# 02_RPI_IO.net
KiCad netlist of a schematic drawn in Altium Designer
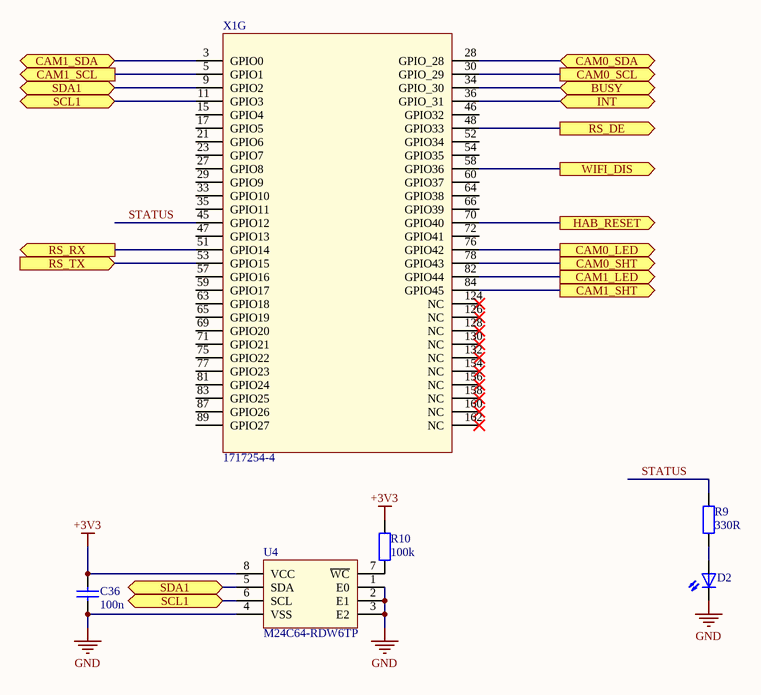
[diagram p0: 02_RPI_IO.SchDoc]

(export (version "E")
  (design (tool "Eeschema 10.0.6"))
  (components
    (comp (ref "C36")
      (value "100n")
      (footprint "C0603_IPC_HD")
      (description "CAP CER 0.1UF 16V X7R 0603")
      (fields
        (field (name "MANUFACTURER") "Samsung Electro-Mechanics")
        (field (name "MANUFACTURER PART NUMBER") "CL10B104KO8NNNC")
      )
      (libsource (lib "alfasat_lib") (part "CL10B104KO8NNNC"))
    )
    (comp (ref "D2")
      (value "LTST-C190GKT")
      (footprint "LED_0603")
      (description "LED GREEN CLEAR CHIP SMD 0603")
      (fields (field (name "MANUFACTURER") "Lite-On Inc."))
      (libsource (lib "alfasat_lib") (part "LTST-C190GKT"))
    )
    (comp (ref "R9")
      (value "330R")
      (footprint "R0603_IPC_MD")
      (description "RES SMD 330 OHM 5% 1/10W 0603")
      (fields
        (field (name "MANUFACTURER") "Bourns Inc.")
        (field (name "MANUFACTURER PART NUMBER") "CR0603-JW-331ELF")
      )
      (libsource (lib "alfasat_lib") (part "CR0603-JW-331ELF"))
    )
    (comp (ref "R10")
      (value "100k")
      (footprint "R0603_IPC_MD")
      (description "RES 100K OHM 1% 1/10W 0603")
      (fields
        (field (name "MANUFACTURER") "Bourns Inc.")
        (field (name "MANUFACTURER PART NUMBER") "RMCF0603FT100K")
      )
      (libsource (lib "alfasat_lib") (part "RMCF0603FT100K"))
    )
    (comp (ref "U4")
      (value "M24C64-RDW6TP")
      (footprint "TSSOP8_(ST)")
      (description "IC EEPROM 64K I2C 1MHZ 8TSSOP")
      (fields (field (name "MANUFACTURER") "STMicroelectronics"))
      (libsource (lib "alfasat_lib") (part "M24C64-RDW6TP"))
    )
    (comp (ref "X1")
      (value "1717254-4")
      (footprint "1717254-1")
      (description "CONN SKT SODIMM 200POS R/A SMD")
      (fields (field (name "MANUFACTURER") "TE Connectivity AMP Connectors"))
      (libsource (lib "alfasat_lib") (part "Raspberry CM Connector"))
    )
  )
  (nets
    (net (code "1") (name "+3V3") (class "Default")
      (node (ref "C36") (pin "2") (pinfunction "2_2") (pintype "passive"))
      (node (ref "R10") (pin "2") (pinfunction "2_2") (pintype "passive"))
      (node (ref "U4") (pin "8") (pinfunction "VCC_8") (pintype "passive"))
    )
    (net (code "2") (name "/BUSY") (class "Default")
      (node (ref "X1") (pin "34") (pinfunction "GPIO_30_34") (pintype "passive"))
    )
    (net (code "3") (name "/CAM0_LED") (class "Default")
      (node (ref "X1") (pin "76") (pinfunction "GPIO42_76") (pintype "passive"))
    )
    (net (code "4") (name "/CAM0_SCL") (class "Default")
      (node (ref "X1") (pin "30") (pinfunction "GPIO_29_30") (pintype "passive"))
    )
    (net (code "5") (name "/CAM0_SDA") (class "Default")
      (node (ref "X1") (pin "28") (pinfunction "GPIO_28_28") (pintype "passive"))
    )
    (net (code "6") (name "/CAM0_SHT") (class "Default")
      (node (ref "X1") (pin "78") (pinfunction "GPIO43_78") (pintype "passive"))
    )
    (net (code "7") (name "/CAM1_LED") (class "Default")
      (node (ref "X1") (pin "82") (pinfunction "GPIO44_82") (pintype "passive"))
    )
    (net (code "8") (name "/CAM1_SCL") (class "Default")
      (node (ref "X1") (pin "5") (pinfunction "GPIO1_5") (pintype "passive"))
    )
    (net (code "9") (name "/CAM1_SDA") (class "Default")
      (node (ref "X1") (pin "3") (pinfunction "GPIO0_3") (pintype "passive"))
    )
    (net (code "10") (name "/CAM1_SHT") (class "Default")
      (node (ref "X1") (pin "84") (pinfunction "GPIO45_84") (pintype "passive"))
    )
    (net (code "11") (name "/HAB_RESET") (class "Default")
      (node (ref "X1") (pin "70") (pinfunction "GPIO40_70") (pintype "passive"))
    )
    (net (code "12") (name "/INT") (class "Default")
      (node (ref "X1") (pin "36") (pinfunction "GPIO_31_36") (pintype "passive"))
    )
    (net (code "13") (name "/RS_DE") (class "Default")
      (node (ref "X1") (pin "48") (pinfunction "GPIO33_48") (pintype "passive"))
    )
    (net (code "14") (name "/RS_RX") (class "Default")
      (node (ref "X1") (pin "51") (pinfunction "GPIO14_51") (pintype "passive"))
    )
    (net (code "15") (name "/RS_TX") (class "Default")
      (node (ref "X1") (pin "53") (pinfunction "GPIO15_53") (pintype "passive"))
    )
    (net (code "16") (name "/SCL1") (class "Default")
      (node (ref "U4") (pin "6") (pinfunction "SCL_6") (pintype "passive"))
      (node (ref "X1") (pin "11") (pinfunction "GPIO3_11") (pintype "passive"))
    )
    (net (code "17") (name "/SDA1") (class "Default")
      (node (ref "U4") (pin "5") (pinfunction "SDA_5") (pintype "passive"))
      (node (ref "X1") (pin "9") (pinfunction "GPIO2_9") (pintype "passive"))
    )
    (net (code "18") (name "/STATUS") (class "Default")
      (node (ref "R9") (pin "2") (pinfunction "2_2") (pintype "passive"))
      (node (ref "X1") (pin "45") (pinfunction "GPIO12_45") (pintype "passive"))
    )
    (net (code "19") (name "/WIFI_DIS") (class "Default")
      (node (ref "X1") (pin "58") (pinfunction "GPIO36_58") (pintype "passive"))
    )
    (net (code "20") (name "GND") (class "Default")
      (node (ref "C36") (pin "1") (pinfunction "1_1") (pintype "passive"))
      (node (ref "D2") (pin "1") (pinfunction "C_1") (pintype "passive"))
      (node (ref "U4") (pin "1") (pinfunction "E0_1") (pintype "passive"))
      (node (ref "U4") (pin "2") (pinfunction "E1_2") (pintype "passive"))
      (node (ref "U4") (pin "3") (pinfunction "E2_3") (pintype "passive"))
      (node (ref "U4") (pin "4") (pinfunction "VSS_4") (pintype "passive"))
    )
    (net (code "21") (name "Net-(D2-A)") (class "Default")
      (node (ref "D2") (pin "2") (pinfunction "A_2") (pintype "passive"))
      (node (ref "R9") (pin "1") (pinfunction "1_1") (pintype "passive"))
    )
    (net (code "22") (name "Net-(U4-~{WC})") (class "Default")
      (node (ref "R10") (pin "1") (pinfunction "1_1") (pintype "passive"))
      (node (ref "U4") (pin "7") (pinfunction "~{WC}_7") (pintype "passive"))
    )
    (net (code "23") (name "unconnected-(X1G-GPIO4-Pad15)") (class "Default")
      (node (ref "X1") (pin "15") (pinfunction "GPIO4_15") (pintype "passive"))
    )
    (net (code "24") (name "unconnected-(X1G-GPIO5-Pad17)") (class "Default")
      (node (ref "X1") (pin "17") (pinfunction "GPIO5_17") (pintype "passive"))
    )
    (net (code "25") (name "unconnected-(X1G-GPIO6-Pad21)") (class "Default")
      (node (ref "X1") (pin "21") (pinfunction "GPIO6_21") (pintype "passive"))
    )
    (net (code "26") (name "unconnected-(X1G-GPIO7-Pad23)") (class "Default")
      (node (ref "X1") (pin "23") (pinfunction "GPIO7_23") (pintype "passive"))
    )
    (net (code "27") (name "unconnected-(X1G-GPIO8-Pad27)") (class "Default")
      (node (ref "X1") (pin "27") (pinfunction "GPIO8_27") (pintype "passive"))
    )
    (net (code "28") (name "unconnected-(X1G-GPIO9-Pad29)") (class "Default")
      (node (ref "X1") (pin "29") (pinfunction "GPIO9_29") (pintype "passive"))
    )
    (net (code "29") (name "unconnected-(X1G-GPIO10-Pad33)") (class "Default")
      (node (ref "X1") (pin "33") (pinfunction "GPIO10_33") (pintype "passive"))
    )
    (net (code "30") (name "unconnected-(X1G-GPIO11-Pad35)") (class "Default")
      (node (ref "X1") (pin "35") (pinfunction "GPIO11_35") (pintype "passive"))
    )
    (net (code "31") (name "unconnected-(X1G-GPIO13-Pad47)") (class "Default")
      (node (ref "X1") (pin "47") (pinfunction "GPIO13_47") (pintype "passive"))
    )
    (net (code "32") (name "unconnected-(X1G-GPIO16-Pad57)") (class "Default")
      (node (ref "X1") (pin "57") (pinfunction "GPIO16_57") (pintype "passive"))
    )
    (net (code "33") (name "unconnected-(X1G-GPIO17-Pad59)") (class "Default")
      (node (ref "X1") (pin "59") (pinfunction "GPIO17_59") (pintype "passive"))
    )
    (net (code "34") (name "unconnected-(X1G-GPIO18-Pad63)") (class "Default")
      (node (ref "X1") (pin "63") (pinfunction "GPIO18_63") (pintype "passive"))
    )
    (net (code "35") (name "unconnected-(X1G-GPIO19-Pad65)") (class "Default")
      (node (ref "X1") (pin "65") (pinfunction "GPIO19_65") (pintype "passive"))
    )
    (net (code "36") (name "unconnected-(X1G-GPIO20-Pad69)") (class "Default")
      (node (ref "X1") (pin "69") (pinfunction "GPIO20_69") (pintype "passive"))
    )
    (net (code "37") (name "unconnected-(X1G-GPIO21-Pad71)") (class "Default")
      (node (ref "X1") (pin "71") (pinfunction "GPIO21_71") (pintype "passive"))
    )
    (net (code "38") (name "unconnected-(X1G-GPIO22-Pad75)") (class "Default")
      (node (ref "X1") (pin "75") (pinfunction "GPIO22_75") (pintype "passive"))
    )
    (net (code "39") (name "unconnected-(X1G-GPIO23-Pad77)") (class "Default")
      (node (ref "X1") (pin "77") (pinfunction "GPIO23_77") (pintype "passive"))
    )
    (net (code "40") (name "unconnected-(X1G-GPIO24-Pad81)") (class "Default")
      (node (ref "X1") (pin "81") (pinfunction "GPIO24_81") (pintype "passive"))
    )
    (net (code "41") (name "unconnected-(X1G-GPIO25-Pad83)") (class "Default")
      (node (ref "X1") (pin "83") (pinfunction "GPIO25_83") (pintype "passive"))
    )
    (net (code "42") (name "unconnected-(X1G-GPIO26-Pad87)") (class "Default")
      (node (ref "X1") (pin "87") (pinfunction "GPIO26_87") (pintype "passive"))
    )
    (net (code "43") (name "unconnected-(X1G-GPIO27-Pad89)") (class "Default")
      (node (ref "X1") (pin "89") (pinfunction "GPIO27_89") (pintype "passive"))
    )
    (net (code "44") (name "unconnected-(X1G-GPIO32-Pad46)") (class "Default")
      (node (ref "X1") (pin "46") (pinfunction "GPIO32_46") (pintype "passive"))
    )
    (net (code "45") (name "unconnected-(X1G-GPIO34-Pad52)") (class "Default")
      (node (ref "X1") (pin "52") (pinfunction "GPIO34_52") (pintype "passive"))
    )
    (net (code "46") (name "unconnected-(X1G-GPIO35-Pad54)") (class "Default")
      (node (ref "X1") (pin "54") (pinfunction "GPIO35_54") (pintype "passive"))
    )
    (net (code "47") (name "unconnected-(X1G-GPIO37-Pad60)") (class "Default")
      (node (ref "X1") (pin "60") (pinfunction "GPIO37_60") (pintype "passive"))
    )
    (net (code "48") (name "unconnected-(X1G-GPIO38-Pad64)") (class "Default")
      (node (ref "X1") (pin "64") (pinfunction "GPIO38_64") (pintype "passive"))
    )
    (net (code "49") (name "unconnected-(X1G-GPIO39-Pad66)") (class "Default")
      (node (ref "X1") (pin "66") (pinfunction "GPIO39_66") (pintype "passive"))
    )
    (net (code "50") (name "unconnected-(X1G-GPIO41-Pad72)") (class "Default")
      (node (ref "X1") (pin "72") (pinfunction "GPIO41_72") (pintype "passive"))
    )
    (net (code "51") (name "unconnected-(X1G-NC-Pad124)") (class "Default")
      (node (ref "X1") (pin "124") (pinfunction "NC_124") (pintype "passive+no_connect"))
    )
    (net (code "52") (name "unconnected-(X1G-NC-Pad126)") (class "Default")
      (node (ref "X1") (pin "126") (pinfunction "NC_126") (pintype "passive+no_connect"))
    )
    (net (code "53") (name "unconnected-(X1G-NC-Pad128)") (class "Default")
      (node (ref "X1") (pin "128") (pinfunction "NC_128") (pintype "passive+no_connect"))
    )
    (net (code "54") (name "unconnected-(X1G-NC-Pad130)") (class "Default")
      (node (ref "X1") (pin "130") (pinfunction "NC_130") (pintype "passive+no_connect"))
    )
    (net (code "55") (name "unconnected-(X1G-NC-Pad132)") (class "Default")
      (node (ref "X1") (pin "132") (pinfunction "NC_132") (pintype "passive+no_connect"))
    )
    (net (code "56") (name "unconnected-(X1G-NC-Pad154)") (class "Default")
      (node (ref "X1") (pin "154") (pinfunction "NC_154") (pintype "passive+no_connect"))
    )
    (net (code "57") (name "unconnected-(X1G-NC-Pad156)") (class "Default")
      (node (ref "X1") (pin "156") (pinfunction "NC_156") (pintype "passive+no_connect"))
    )
    (net (code "58") (name "unconnected-(X1G-NC-Pad158)") (class "Default")
      (node (ref "X1") (pin "158") (pinfunction "NC_158") (pintype "passive+no_connect"))
    )
    (net (code "59") (name "unconnected-(X1G-NC-Pad160)") (class "Default")
      (node (ref "X1") (pin "160") (pinfunction "NC_160") (pintype "passive+no_connect"))
    )
    (net (code "60") (name "unconnected-(X1G-NC-Pad162)") (class "Default")
      (node (ref "X1") (pin "162") (pinfunction "NC_162") (pintype "passive+no_connect"))
    )
  )
)
